# fuel.net
KiCad netlist of a schematic drawn in EAGLE
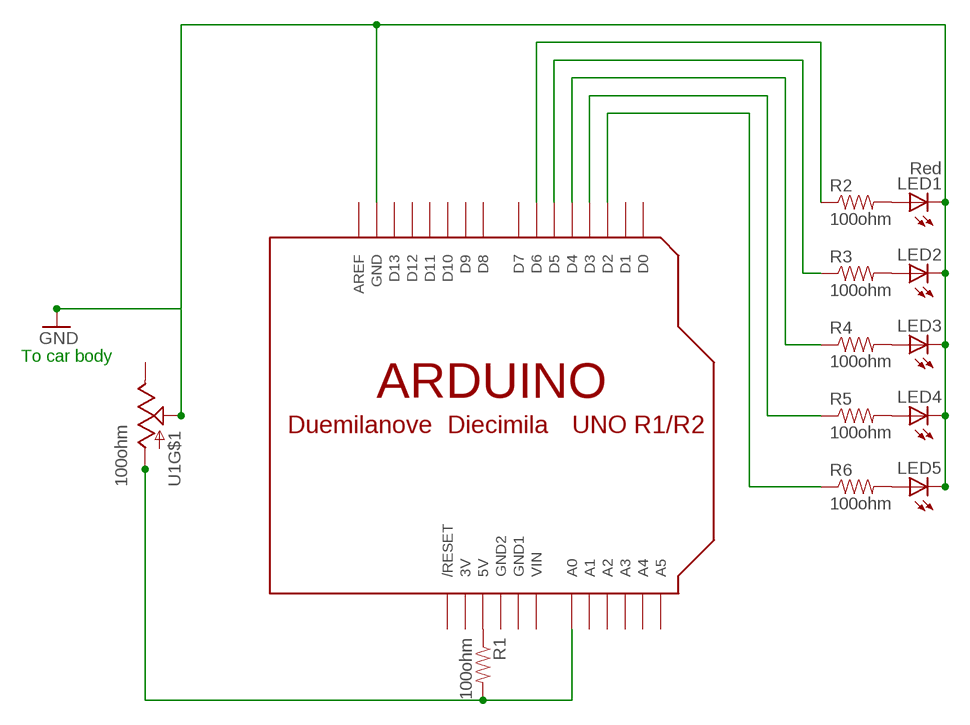
[diagram p0: schematic, sheet 1]

(export (version "E")
  (design (tool "Eeschema 10.0.6"))
  (components
    (comp (ref "LED1")
      (value "Red")
      (footprint "eagle-import:Q62902-B152")
      (libsource (lib "eagle-import") (part "LEDB152"))
    )
    (comp (ref "LED2")
      (value "LEDB152")
      (footprint "eagle-import:Q62902-B152")
      (libsource (lib "eagle-import") (part "LEDB152"))
    )
    (comp (ref "LED3")
      (value "LEDB152")
      (footprint "eagle-import:Q62902-B152")
      (libsource (lib "eagle-import") (part "LEDB152"))
    )
    (comp (ref "LED4")
      (value "LEDB152")
      (footprint "eagle-import:Q62902-B152")
      (libsource (lib "eagle-import") (part "LEDB152"))
    )
    (comp (ref "LED5")
      (value "LEDB152")
      (footprint "eagle-import:Q62902-B152")
      (libsource (lib "eagle-import") (part "LEDB152"))
    )
    (comp (ref "R1")
      (value "100ohm")
      (footprint "eagle-import:0402-RES")
      (libsource (lib "eagle-import") (part "RESISTOR0402-RES"))
    )
    (comp (ref "R2")
      (value "100ohm")
      (footprint "eagle-import:0402-RES")
      (libsource (lib "eagle-import") (part "RESISTOR0402-RES"))
    )
    (comp (ref "R3")
      (value "100ohm")
      (footprint "eagle-import:0402-RES")
      (libsource (lib "eagle-import") (part "RESISTOR0402-RES"))
    )
    (comp (ref "R4")
      (value "100ohm")
      (footprint "eagle-import:0402-RES")
      (libsource (lib "eagle-import") (part "RESISTOR0402-RES"))
    )
    (comp (ref "R5")
      (value "100ohm")
      (footprint "eagle-import:0402-RES")
      (libsource (lib "eagle-import") (part "RESISTOR0402-RES"))
    )
    (comp (ref "R6")
      (value "100ohm")
      (footprint "eagle-import:0402-RES")
      (libsource (lib "eagle-import") (part "RESISTOR0402-RES"))
    )
    (comp (ref "U$1")
      (value "ARDUINOUNO")
      (footprint "eagle-import:ARDUINO")
      (libsource (lib "eagle-import") (part "ARDUINOUNO"))
    )
    (comp (ref "U1")
      (value "100ohm")
      (footprint "eagle-import:POT_PTH")
      (libsource (lib "eagle-import") (part "POT_SWITCHPOT_PTH"))
    )
  )
  (nets
    (net (code "1") (name "/3V") (class "Default")
      (node (ref "U$1") (pin "3V") (pinfunction "3V_3V") (pintype "power_in"))
    )
    (net (code "2") (name "/GND1") (class "Default")
      (node (ref "U$1") (pin "GND1") (pinfunction "GND1_GND1") (pintype "power_in"))
    )
    (net (code "3") (name "/GND2") (class "Default")
      (node (ref "U$1") (pin "GND2") (pinfunction "GND2_GND2") (pintype "power_in"))
    )
    (net (code "4") (name "/VIN") (class "Default")
      (node (ref "U$1") (pin "VIN") (pinfunction "VIN_VIN") (pintype "power_in"))
    )
    (net (code "5") (name "GND") (class "Default")
      (node (ref "LED1") (pin "K") (pinfunction "C_K") (pintype "passive"))
      (node (ref "LED2") (pin "K") (pinfunction "C_K") (pintype "passive"))
      (node (ref "LED3") (pin "K") (pinfunction "C_K") (pintype "passive"))
      (node (ref "LED4") (pin "K") (pinfunction "C_K") (pintype "passive"))
      (node (ref "LED5") (pin "K") (pinfunction "C_K") (pintype "passive"))
      (node (ref "U$1") (pin "GND") (pinfunction "GND_GND") (pintype "power_in"))
      (node (ref "U1") (pin "WAND") (pinfunction "S_WAND") (pintype "passive"))
    )
    (net (code "6") (name "Net-(LED1-PadA)") (class "Default")
      (node (ref "LED1") (pin "A") (pinfunction "A_A") (pintype "passive"))
      (node (ref "R2") (pin "2") (pinfunction "2_2") (pintype "passive"))
    )
    (net (code "7") (name "Net-(LED2-PadA)") (class "Default")
      (node (ref "LED2") (pin "A") (pinfunction "A_A") (pintype "passive"))
      (node (ref "R3") (pin "2") (pinfunction "2_2") (pintype "passive"))
    )
    (net (code "8") (name "Net-(LED3-PadA)") (class "Default")
      (node (ref "LED3") (pin "A") (pinfunction "A_A") (pintype "passive"))
      (node (ref "R4") (pin "2") (pinfunction "2_2") (pintype "passive"))
    )
    (net (code "9") (name "Net-(LED4-PadA)") (class "Default")
      (node (ref "LED4") (pin "A") (pinfunction "A_A") (pintype "passive"))
      (node (ref "R5") (pin "2") (pinfunction "2_2") (pintype "passive"))
    )
    (net (code "10") (name "Net-(LED5-PadA)") (class "Default")
      (node (ref "LED5") (pin "A") (pinfunction "A_A") (pintype "passive"))
      (node (ref "R6") (pin "2") (pinfunction "2_2") (pintype "passive"))
    )
    (net (code "11") (name "Net-(R1-Pad1)") (class "Default")
      (node (ref "R1") (pin "1") (pinfunction "1_1") (pintype "passive"))
      (node (ref "U$1") (pin "5V") (pinfunction "5V_5V") (pintype "power_in"))
    )
    (net (code "12") (name "Net-(R2-Pad1)") (class "Default")
      (node (ref "R2") (pin "1") (pinfunction "1_1") (pintype "passive"))
      (node (ref "U$1") (pin "D6") (pinfunction "D6_D6") (pintype "bidirectional"))
    )
    (net (code "13") (name "Net-(R3-Pad1)") (class "Default")
      (node (ref "R3") (pin "1") (pinfunction "1_1") (pintype "passive"))
      (node (ref "U$1") (pin "D5") (pinfunction "D5_D5") (pintype "bidirectional"))
    )
    (net (code "14") (name "Net-(R4-Pad1)") (class "Default")
      (node (ref "R4") (pin "1") (pinfunction "1_1") (pintype "passive"))
      (node (ref "U$1") (pin "D4") (pinfunction "D4_D4") (pintype "bidirectional"))
    )
    (net (code "15") (name "Net-(R5-Pad1)") (class "Default")
      (node (ref "R5") (pin "1") (pinfunction "1_1") (pintype "passive"))
      (node (ref "U$1") (pin "D3") (pinfunction "D3_D3") (pintype "bidirectional"))
    )
    (net (code "16") (name "Net-(R6-Pad1)") (class "Default")
      (node (ref "R6") (pin "1") (pinfunction "1_1") (pintype "passive"))
      (node (ref "U$1") (pin "D2") (pinfunction "D2_D2") (pintype "bidirectional"))
    )
    (net (code "17") (name "Net-(U1A-A)") (class "Default")
      (node (ref "R1") (pin "2") (pinfunction "2_2") (pintype "passive"))
      (node (ref "U$1") (pin "A0") (pinfunction "A0_A0") (pintype "bidirectional"))
      (node (ref "U1") (pin "E@1") (pinfunction "A_E@1") (pintype "passive"))
    )
    (net (code "18") (name "unconnected-(U$1-PadA1)") (class "Default")
      (node (ref "U$1") (pin "A1") (pinfunction "A1_A1") (pintype "bidirectional"))
    )
    (net (code "19") (name "unconnected-(U$1-PadA2)") (class "Default")
      (node (ref "U$1") (pin "A2") (pinfunction "A2_A2") (pintype "bidirectional"))
    )
    (net (code "20") (name "unconnected-(U$1-PadA3)") (class "Default")
      (node (ref "U$1") (pin "A3") (pinfunction "A3_A3") (pintype "bidirectional"))
    )
    (net (code "21") (name "unconnected-(U$1-PadA4)") (class "Default")
      (node (ref "U$1") (pin "A4") (pinfunction "A4_A4") (pintype "bidirectional"))
    )
    (net (code "22") (name "unconnected-(U$1-PadA5)") (class "Default")
      (node (ref "U$1") (pin "A5") (pinfunction "A5_A5") (pintype "bidirectional"))
    )
    (net (code "23") (name "unconnected-(U$1-PadAREF)") (class "Default")
      (node (ref "U$1") (pin "AREF") (pinfunction "AREF_AREF") (pintype "bidirectional"))
    )
    (net (code "24") (name "unconnected-(U$1-PadD0)") (class "Default")
      (node (ref "U$1") (pin "D0") (pinfunction "D0_D0") (pintype "bidirectional"))
    )
    (net (code "25") (name "unconnected-(U$1-PadD1)") (class "Default")
      (node (ref "U$1") (pin "D1") (pinfunction "D1_D1") (pintype "bidirectional"))
    )
    (net (code "26") (name "unconnected-(U$1-PadD7)") (class "Default")
      (node (ref "U$1") (pin "D7") (pinfunction "D7_D7") (pintype "bidirectional"))
    )
    (net (code "27") (name "unconnected-(U$1-PadD8)") (class "Default")
      (node (ref "U$1") (pin "D8") (pinfunction "D8_D8") (pintype "bidirectional"))
    )
    (net (code "28") (name "unconnected-(U$1-PadD9)") (class "Default")
      (node (ref "U$1") (pin "D9") (pinfunction "D9_D9") (pintype "bidirectional"))
    )
    (net (code "29") (name "unconnected-(U$1-PadD10)") (class "Default")
      (node (ref "U$1") (pin "D10") (pinfunction "D10_D10") (pintype "bidirectional"))
    )
    (net (code "30") (name "unconnected-(U$1-PadD11)") (class "Default")
      (node (ref "U$1") (pin "D11") (pinfunction "D11_D11") (pintype "bidirectional"))
    )
    (net (code "31") (name "unconnected-(U$1-PadD12)") (class "Default")
      (node (ref "U$1") (pin "D12") (pinfunction "D12_D12") (pintype "bidirectional"))
    )
    (net (code "32") (name "unconnected-(U$1-PadD13)") (class "Default")
      (node (ref "U$1") (pin "D13") (pinfunction "D13_D13") (pintype "bidirectional"))
    )
    (net (code "33") (name "unconnected-(U$1-{slash}RESET-PadRESET)") (class "Default")
      (node (ref "U$1") (pin "RESET") (pinfunction "/RESET_RESET") (pintype "bidirectional"))
    )
    (net (code "34") (name "unconnected-(U1A-E-PadE@2)") (class "Default")
      (node (ref "U1") (pin "E@2") (pinfunction "E_E@2") (pintype "passive"))
    )
  )
)
